# fnordstripe.net
KiCad netlist of a schematic drawn in EAGLE
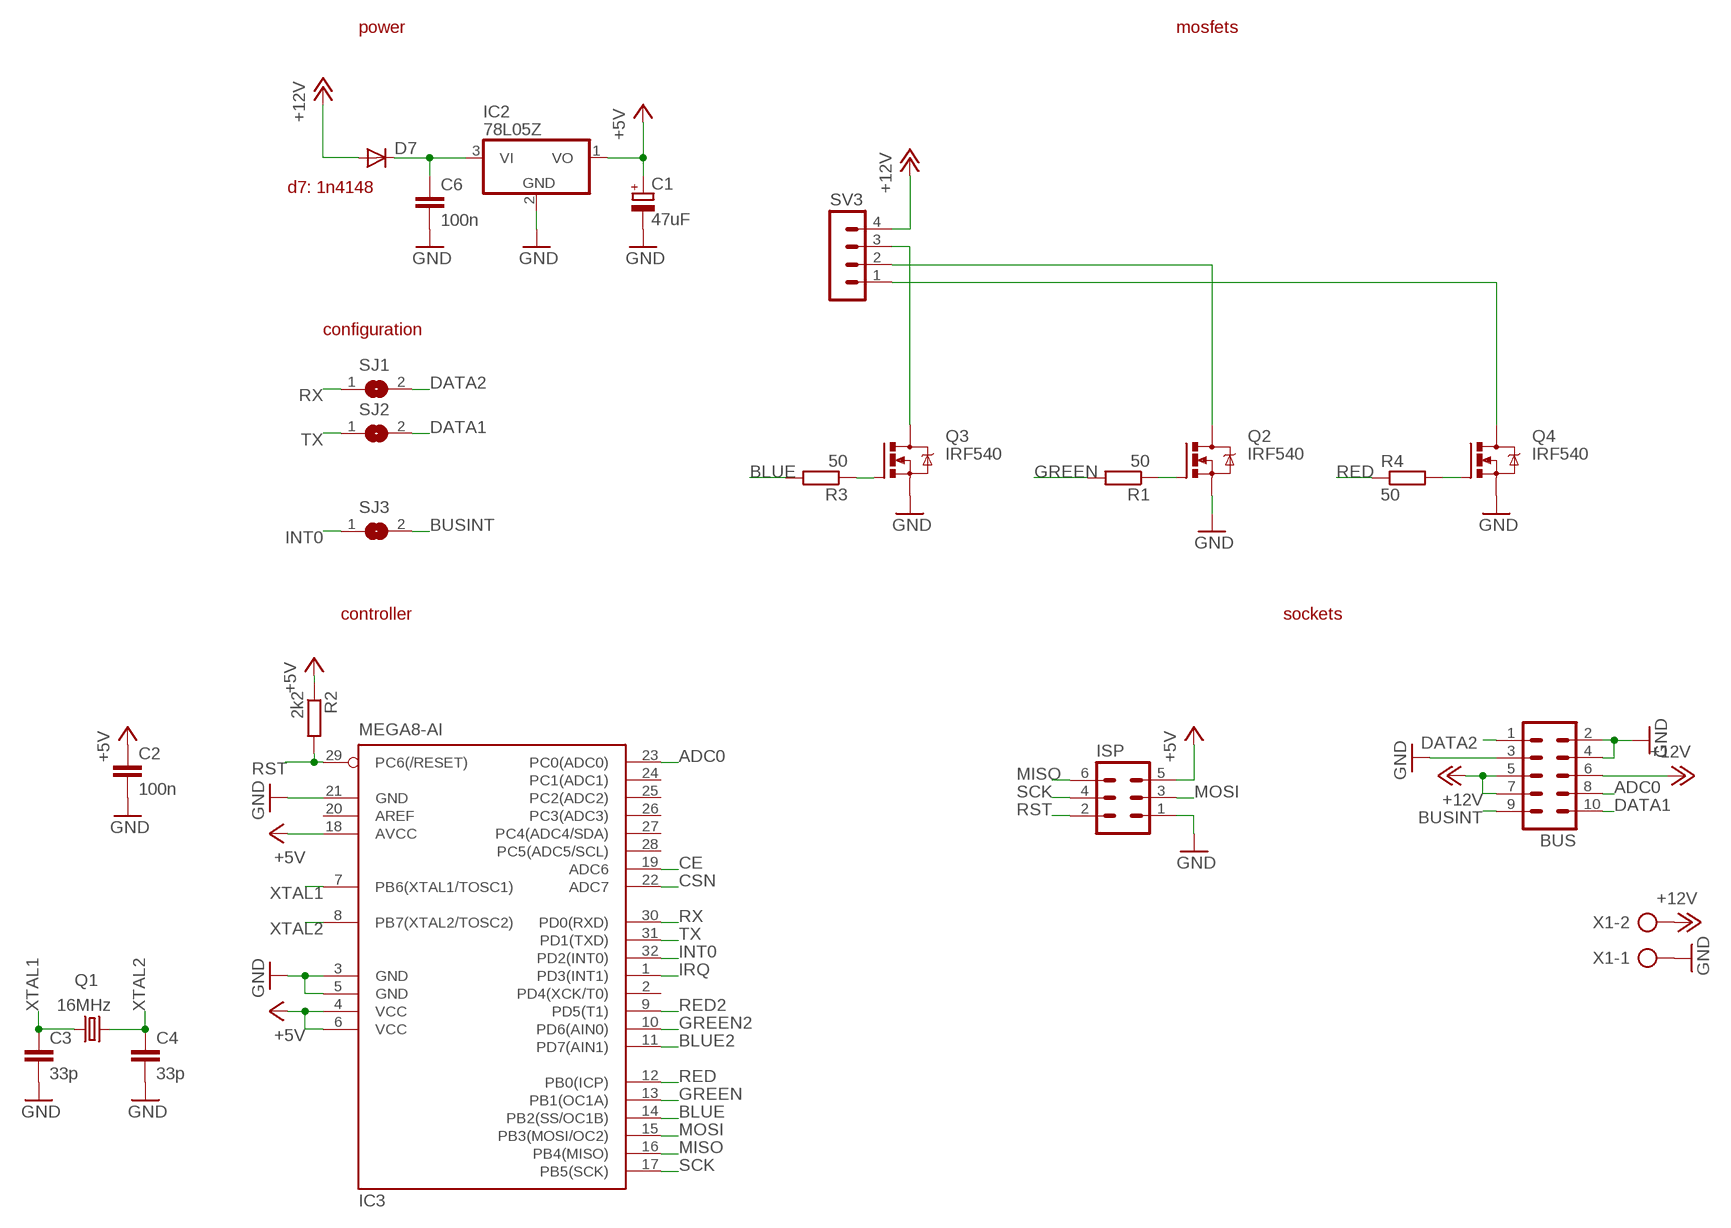
[diagram p0: schematic, sheet 1]

(export (version "E")
  (design (tool "Eeschema 10.0.6"))
  (components
    (comp (ref "BUS")
      (value "MA05-2")
      (footprint "eagle-import:MA05-2")
      (libsource (lib "eagle-import") (part "MA05-2"))
    )
    (comp (ref "C1")
      (value "47uF")
      (footprint "eagle-import:E2-5")
      (libsource (lib "eagle-import") (part "CPOL-EUE2-5"))
    )
    (comp (ref "C2")
      (value "100n")
      (footprint "eagle-import:C025-024X044")
      (libsource (lib "eagle-import") (part "C-EU025-024X044"))
    )
    (comp (ref "C3")
      (value "33p")
      (footprint "eagle-import:C025-024X044")
      (libsource (lib "eagle-import") (part "C-EU025-024X044"))
    )
    (comp (ref "C4")
      (value "33p")
      (footprint "eagle-import:C025-024X044")
      (libsource (lib "eagle-import") (part "C-EU025-024X044"))
    )
    (comp (ref "C6")
      (value "100n")
      (footprint "eagle-import:C025-024X044")
      (libsource (lib "eagle-import") (part "C-EU025-024X044"))
    )
    (comp (ref "D7")
      (value "DIODE-D-2.5")
      (footprint "eagle-import:D-2.5")
      (libsource (lib "eagle-import") (part "DIODE-D-2.5"))
    )
    (comp (ref "IC2")
      (value "78L05Z")
      (footprint "eagle-import:TO92")
      (libsource (lib "eagle-import") (part "78ZL05"))
    )
    (comp (ref "IC3")
      (value "MEGA8-AI")
      (footprint "eagle-import:TQFP32-08")
      (fields (field (name "MPN") "ATMEGA8-16AU"))
      (libsource (lib "eagle-import") (part "MEGA8-AI"))
    )
    (comp (ref "ISP")
      (value "MA03-2")
      (footprint "eagle-import:MA03-2")
      (libsource (lib "eagle-import") (part "MA03-2"))
    )
    (comp (ref "Q1")
      (value "16MHz")
      (footprint "eagle-import:HC49U-V")
      (libsource (lib "eagle-import") (part "CRYSTALHC49U-V"))
    )
    (comp (ref "Q2")
      (value "IRF540")
      (footprint "eagle-import:TO220BV")
      (libsource (lib "eagle-import") (part "IRF540"))
    )
    (comp (ref "Q3")
      (value "IRF540")
      (footprint "eagle-import:TO220BV")
      (libsource (lib "eagle-import") (part "IRF540"))
    )
    (comp (ref "Q4")
      (value "IRF540")
      (footprint "eagle-import:TO220BV")
      (libsource (lib "eagle-import") (part "IRF540"))
    )
    (comp (ref "R1")
      (value "50")
      (footprint "eagle-import:0204V")
      (libsource (lib "eagle-import") (part "R-EU_0204/2V"))
    )
    (comp (ref "R2")
      (value "2k2")
      (footprint "eagle-import:0204V")
      (libsource (lib "eagle-import") (part "R-EU_0204/2V"))
    )
    (comp (ref "R3")
      (value "50")
      (footprint "eagle-import:0204V")
      (libsource (lib "eagle-import") (part "R-EU_0204/2V"))
    )
    (comp (ref "R4")
      (value "50")
      (footprint "eagle-import:0204V")
      (libsource (lib "eagle-import") (part "R-EU_0204/2V"))
    )
    (comp (ref "SJ1") (value "SJ") (footprint "eagle-import:SJ") (libsource (lib "eagle-import") (part "SJ")))
    (comp (ref "SJ2") (value "SJ") (footprint "eagle-import:SJ") (libsource (lib "eagle-import") (part "SJ")))
    (comp (ref "SJ3") (value "SJ") (footprint "eagle-import:SJ") (libsource (lib "eagle-import") (part "SJ")))
    (comp (ref "SV3")
      (value "MA04-1")
      (footprint "eagle-import:MA04-1")
      (libsource (lib "eagle-import") (part "MA04-1"))
    )
    (comp (ref "X1")
      (value "AK500/2")
      (footprint "eagle-import:AK500_2")
      (libsource (lib "eagle-import") (part "AK500/2"))
    )
  )
  (nets
    (net (code "1") (name "+5V") (class "Default")
      (node (ref "C1") (pin "+") (pinfunction "+_+") (pintype "passive"))
      (node (ref "C2") (pin "1") (pinfunction "1_1") (pintype "passive"))
      (node (ref "IC2") (pin "1") (pinfunction "VO_1") (pintype "passive"))
      (node (ref "IC3") (pin "18") (pinfunction "AVCC_18") (pintype "power_in"))
      (node (ref "IC3") (pin "4") (pinfunction "VCC_4") (pintype "power_in"))
      (node (ref "IC3") (pin "6") (pinfunction "VCC_6") (pintype "power_in"))
      (node (ref "ISP") (pin "5") (pinfunction "5_5") (pintype "passive"))
      (node (ref "R2") (pin "1") (pinfunction "1_1") (pintype "passive"))
    )
    (net (code "2") (name "+12V") (class "Default")
      (node (ref "BUS") (pin "5") (pinfunction "5_5") (pintype "passive"))
      (node (ref "BUS") (pin "6") (pinfunction "6_6") (pintype "passive"))
      (node (ref "BUS") (pin "7") (pinfunction "7_7") (pintype "passive"))
      (node (ref "D7") (pin "A") (pinfunction "A_A") (pintype "passive"))
      (node (ref "SV3") (pin "4") (pinfunction "4_4") (pintype "passive"))
      (node (ref "X1") (pin "2") (pinfunction "KL_2") (pintype "passive"))
    )
    (net (code "3") (name "/ADC0") (class "Default")
      (node (ref "BUS") (pin "8") (pinfunction "8_8") (pintype "passive"))
      (node (ref "IC3") (pin "23") (pinfunction "PC0(ADC0)_23") (pintype "bidirectional"))
    )
    (net (code "4") (name "/BLUE") (class "Default")
      (node (ref "IC3") (pin "14") (pinfunction "PB2(SS/OC1B)_14") (pintype "bidirectional"))
      (node (ref "R3") (pin "2") (pinfunction "2_2") (pintype "passive"))
    )
    (net (code "5") (name "/BLUE2") (class "Default")
      (node (ref "IC3") (pin "11") (pinfunction "PD7(AIN1)_11") (pintype "bidirectional"))
    )
    (net (code "6") (name "/BUSINT") (class "Default")
      (node (ref "BUS") (pin "9") (pinfunction "9_9") (pintype "passive"))
      (node (ref "SJ3") (pin "2") (pinfunction "2_2") (pintype "passive"))
    )
    (net (code "7") (name "/CE") (class "Default")
      (node (ref "IC3") (pin "19") (pinfunction "ADC6_19") (pintype "bidirectional"))
    )
    (net (code "8") (name "/CSN") (class "Default")
      (node (ref "IC3") (pin "22") (pinfunction "ADC7_22") (pintype "bidirectional"))
    )
    (net (code "9") (name "/DATA1") (class "Default")
      (node (ref "BUS") (pin "10") (pinfunction "10_10") (pintype "passive"))
      (node (ref "SJ2") (pin "2") (pinfunction "2_2") (pintype "passive"))
    )
    (net (code "10") (name "/DATA2") (class "Default")
      (node (ref "BUS") (pin "1") (pinfunction "1_1") (pintype "passive"))
      (node (ref "SJ1") (pin "2") (pinfunction "2_2") (pintype "passive"))
    )
    (net (code "11") (name "/GREEN") (class "Default")
      (node (ref "IC3") (pin "13") (pinfunction "PB1(OC1A)_13") (pintype "bidirectional"))
      (node (ref "R1") (pin "2") (pinfunction "2_2") (pintype "passive"))
    )
    (net (code "12") (name "/GREEN2") (class "Default")
      (node (ref "IC3") (pin "10") (pinfunction "PD6(AIN0)_10") (pintype "bidirectional"))
    )
    (net (code "13") (name "/INT0") (class "Default")
      (node (ref "IC3") (pin "32") (pinfunction "PD2(INT0)_32") (pintype "bidirectional"))
      (node (ref "SJ3") (pin "1") (pinfunction "1_1") (pintype "passive"))
    )
    (net (code "14") (name "/IRQ") (class "Default")
      (node (ref "IC3") (pin "1") (pinfunction "PD3(INT1)_1") (pintype "bidirectional"))
    )
    (net (code "15") (name "/MISO") (class "Default")
      (node (ref "IC3") (pin "16") (pinfunction "PB4(MISO)_16") (pintype "bidirectional"))
      (node (ref "ISP") (pin "6") (pinfunction "6_6") (pintype "passive"))
    )
    (net (code "16") (name "/MOSI") (class "Default")
      (node (ref "IC3") (pin "15") (pinfunction "PB3(MOSI/OC2)_15") (pintype "bidirectional"))
      (node (ref "ISP") (pin "3") (pinfunction "3_3") (pintype "passive"))
    )
    (net (code "17") (name "/RED") (class "Default")
      (node (ref "IC3") (pin "12") (pinfunction "PB0(ICP)_12") (pintype "bidirectional"))
      (node (ref "R4") (pin "1") (pinfunction "1_1") (pintype "passive"))
    )
    (net (code "18") (name "/RED2") (class "Default")
      (node (ref "IC3") (pin "9") (pinfunction "PD5(T1)_9") (pintype "bidirectional"))
    )
    (net (code "19") (name "/RST") (class "Default")
      (node (ref "IC3") (pin "29") (pinfunction "PC6(/RESET)_29") (pintype "bidirectional"))
      (node (ref "ISP") (pin "2") (pinfunction "2_2") (pintype "passive"))
      (node (ref "R2") (pin "2") (pinfunction "2_2") (pintype "passive"))
    )
    (net (code "20") (name "/RX") (class "Default")
      (node (ref "IC3") (pin "30") (pinfunction "PD0(RXD)_30") (pintype "bidirectional"))
      (node (ref "SJ1") (pin "1") (pinfunction "1_1") (pintype "passive"))
    )
    (net (code "21") (name "/SCK") (class "Default")
      (node (ref "IC3") (pin "17") (pinfunction "PB5(SCK)_17") (pintype "bidirectional"))
      (node (ref "ISP") (pin "4") (pinfunction "4_4") (pintype "passive"))
    )
    (net (code "22") (name "/TX") (class "Default")
      (node (ref "IC3") (pin "31") (pinfunction "PD1(TXD)_31") (pintype "bidirectional"))
      (node (ref "SJ2") (pin "1") (pinfunction "1_1") (pintype "passive"))
    )
    (net (code "23") (name "/XTAL1") (class "Default")
      (node (ref "C3") (pin "1") (pinfunction "1_1") (pintype "passive"))
      (node (ref "IC3") (pin "7") (pinfunction "PB6(XTAL1/TOSC1)_7") (pintype "bidirectional"))
      (node (ref "Q1") (pin "1") (pinfunction "1_1") (pintype "passive"))
    )
    (net (code "24") (name "/XTAL2") (class "Default")
      (node (ref "C4") (pin "1") (pinfunction "1_1") (pintype "passive"))
      (node (ref "IC3") (pin "8") (pinfunction "PB7(XTAL2/TOSC2)_8") (pintype "bidirectional"))
      (node (ref "Q1") (pin "2") (pinfunction "2_2") (pintype "passive"))
    )
    (net (code "25") (name "GND") (class "Default")
      (node (ref "BUS") (pin "2") (pinfunction "2_2") (pintype "passive"))
      (node (ref "BUS") (pin "3") (pinfunction "3_3") (pintype "passive"))
      (node (ref "BUS") (pin "4") (pinfunction "4_4") (pintype "passive"))
      (node (ref "C1") (pin "-") (pinfunction "-_-") (pintype "passive"))
      (node (ref "C2") (pin "2") (pinfunction "2_2") (pintype "passive"))
      (node (ref "C3") (pin "2") (pinfunction "2_2") (pintype "passive"))
      (node (ref "C4") (pin "2") (pinfunction "2_2") (pintype "passive"))
      (node (ref "C6") (pin "2") (pinfunction "2_2") (pintype "passive"))
      (node (ref "IC2") (pin "2") (pinfunction "GND_2") (pintype "passive"))
      (node (ref "IC3") (pin "21") (pinfunction "GND_21") (pintype "power_in"))
      (node (ref "IC3") (pin "3") (pinfunction "GND_3") (pintype "power_in"))
      (node (ref "IC3") (pin "5") (pinfunction "GND_5") (pintype "power_in"))
      (node (ref "ISP") (pin "1") (pinfunction "1_1") (pintype "passive"))
      (node (ref "Q2") (pin "S") (pinfunction "S_S") (pintype "passive"))
      (node (ref "Q3") (pin "S") (pinfunction "S_S") (pintype "passive"))
      (node (ref "Q4") (pin "S") (pinfunction "S_S") (pintype "passive"))
      (node (ref "X1") (pin "1") (pinfunction "KL_1") (pintype "passive"))
    )
    (net (code "26") (name "Net-(IC2-VI)") (class "Default")
      (node (ref "C6") (pin "1") (pinfunction "1_1") (pintype "passive"))
      (node (ref "D7") (pin "C") (pinfunction "C_C") (pintype "passive"))
      (node (ref "IC2") (pin "3") (pinfunction "VI_3") (pintype "input"))
    )
    (net (code "27") (name "Net-(Q2-PadD)") (class "Default")
      (node (ref "Q2") (pin "D") (pinfunction "D_D") (pintype "passive"))
      (node (ref "SV3") (pin "2") (pinfunction "2_2") (pintype "passive"))
    )
    (net (code "28") (name "Net-(Q2-PadG)") (class "Default")
      (node (ref "Q2") (pin "G") (pinfunction "G_G") (pintype "passive"))
      (node (ref "R1") (pin "1") (pinfunction "1_1") (pintype "passive"))
    )
    (net (code "29") (name "Net-(Q3-PadD)") (class "Default")
      (node (ref "Q3") (pin "D") (pinfunction "D_D") (pintype "passive"))
      (node (ref "SV3") (pin "3") (pinfunction "3_3") (pintype "passive"))
    )
    (net (code "30") (name "Net-(Q3-PadG)") (class "Default")
      (node (ref "Q3") (pin "G") (pinfunction "G_G") (pintype "passive"))
      (node (ref "R3") (pin "1") (pinfunction "1_1") (pintype "passive"))
    )
    (net (code "31") (name "Net-(Q4-PadD)") (class "Default")
      (node (ref "Q4") (pin "D") (pinfunction "D_D") (pintype "passive"))
      (node (ref "SV3") (pin "1") (pinfunction "1_1") (pintype "passive"))
    )
    (net (code "32") (name "Net-(Q4-PadG)") (class "Default")
      (node (ref "Q4") (pin "G") (pinfunction "G_G") (pintype "passive"))
      (node (ref "R4") (pin "2") (pinfunction "2_2") (pintype "passive"))
    )
    (net (code "33") (name "unconnected-(IC3-AREF-Pad20)") (class "Default")
      (node (ref "IC3") (pin "20") (pinfunction "AREF_20") (pintype "passive"))
    )
    (net (code "34") (name "unconnected-(IC3-PC1(ADC1)-Pad24)") (class "Default")
      (node (ref "IC3") (pin "24") (pinfunction "PC1(ADC1)_24") (pintype "bidirectional"))
    )
    (net (code "35") (name "unconnected-(IC3-PC2(ADC2)-Pad25)") (class "Default")
      (node (ref "IC3") (pin "25") (pinfunction "PC2(ADC2)_25") (pintype "bidirectional"))
    )
    (net (code "36") (name "unconnected-(IC3-PC3(ADC3)-Pad26)") (class "Default")
      (node (ref "IC3") (pin "26") (pinfunction "PC3(ADC3)_26") (pintype "bidirectional"))
    )
    (net (code "37") (name "unconnected-(IC3-PC4(ADC4{slash}SDA)-Pad27)") (class "Default")
      (node (ref "IC3") (pin "27") (pinfunction "PC4(ADC4/SDA)_27") (pintype "bidirectional"))
    )
    (net (code "38") (name "unconnected-(IC3-PC5(ADC5{slash}SCL)-Pad28)") (class "Default")
      (node (ref "IC3") (pin "28") (pinfunction "PC5(ADC5/SCL)_28") (pintype "bidirectional"))
    )
    (net (code "39") (name "unconnected-(IC3-PD4(XCK{slash}T0)-Pad2)") (class "Default")
      (node (ref "IC3") (pin "2") (pinfunction "PD4(XCK/T0)_2") (pintype "bidirectional"))
    )
  )
)
